# schaltplan.net
KiCad netlist of a schematic drawn in EAGLE
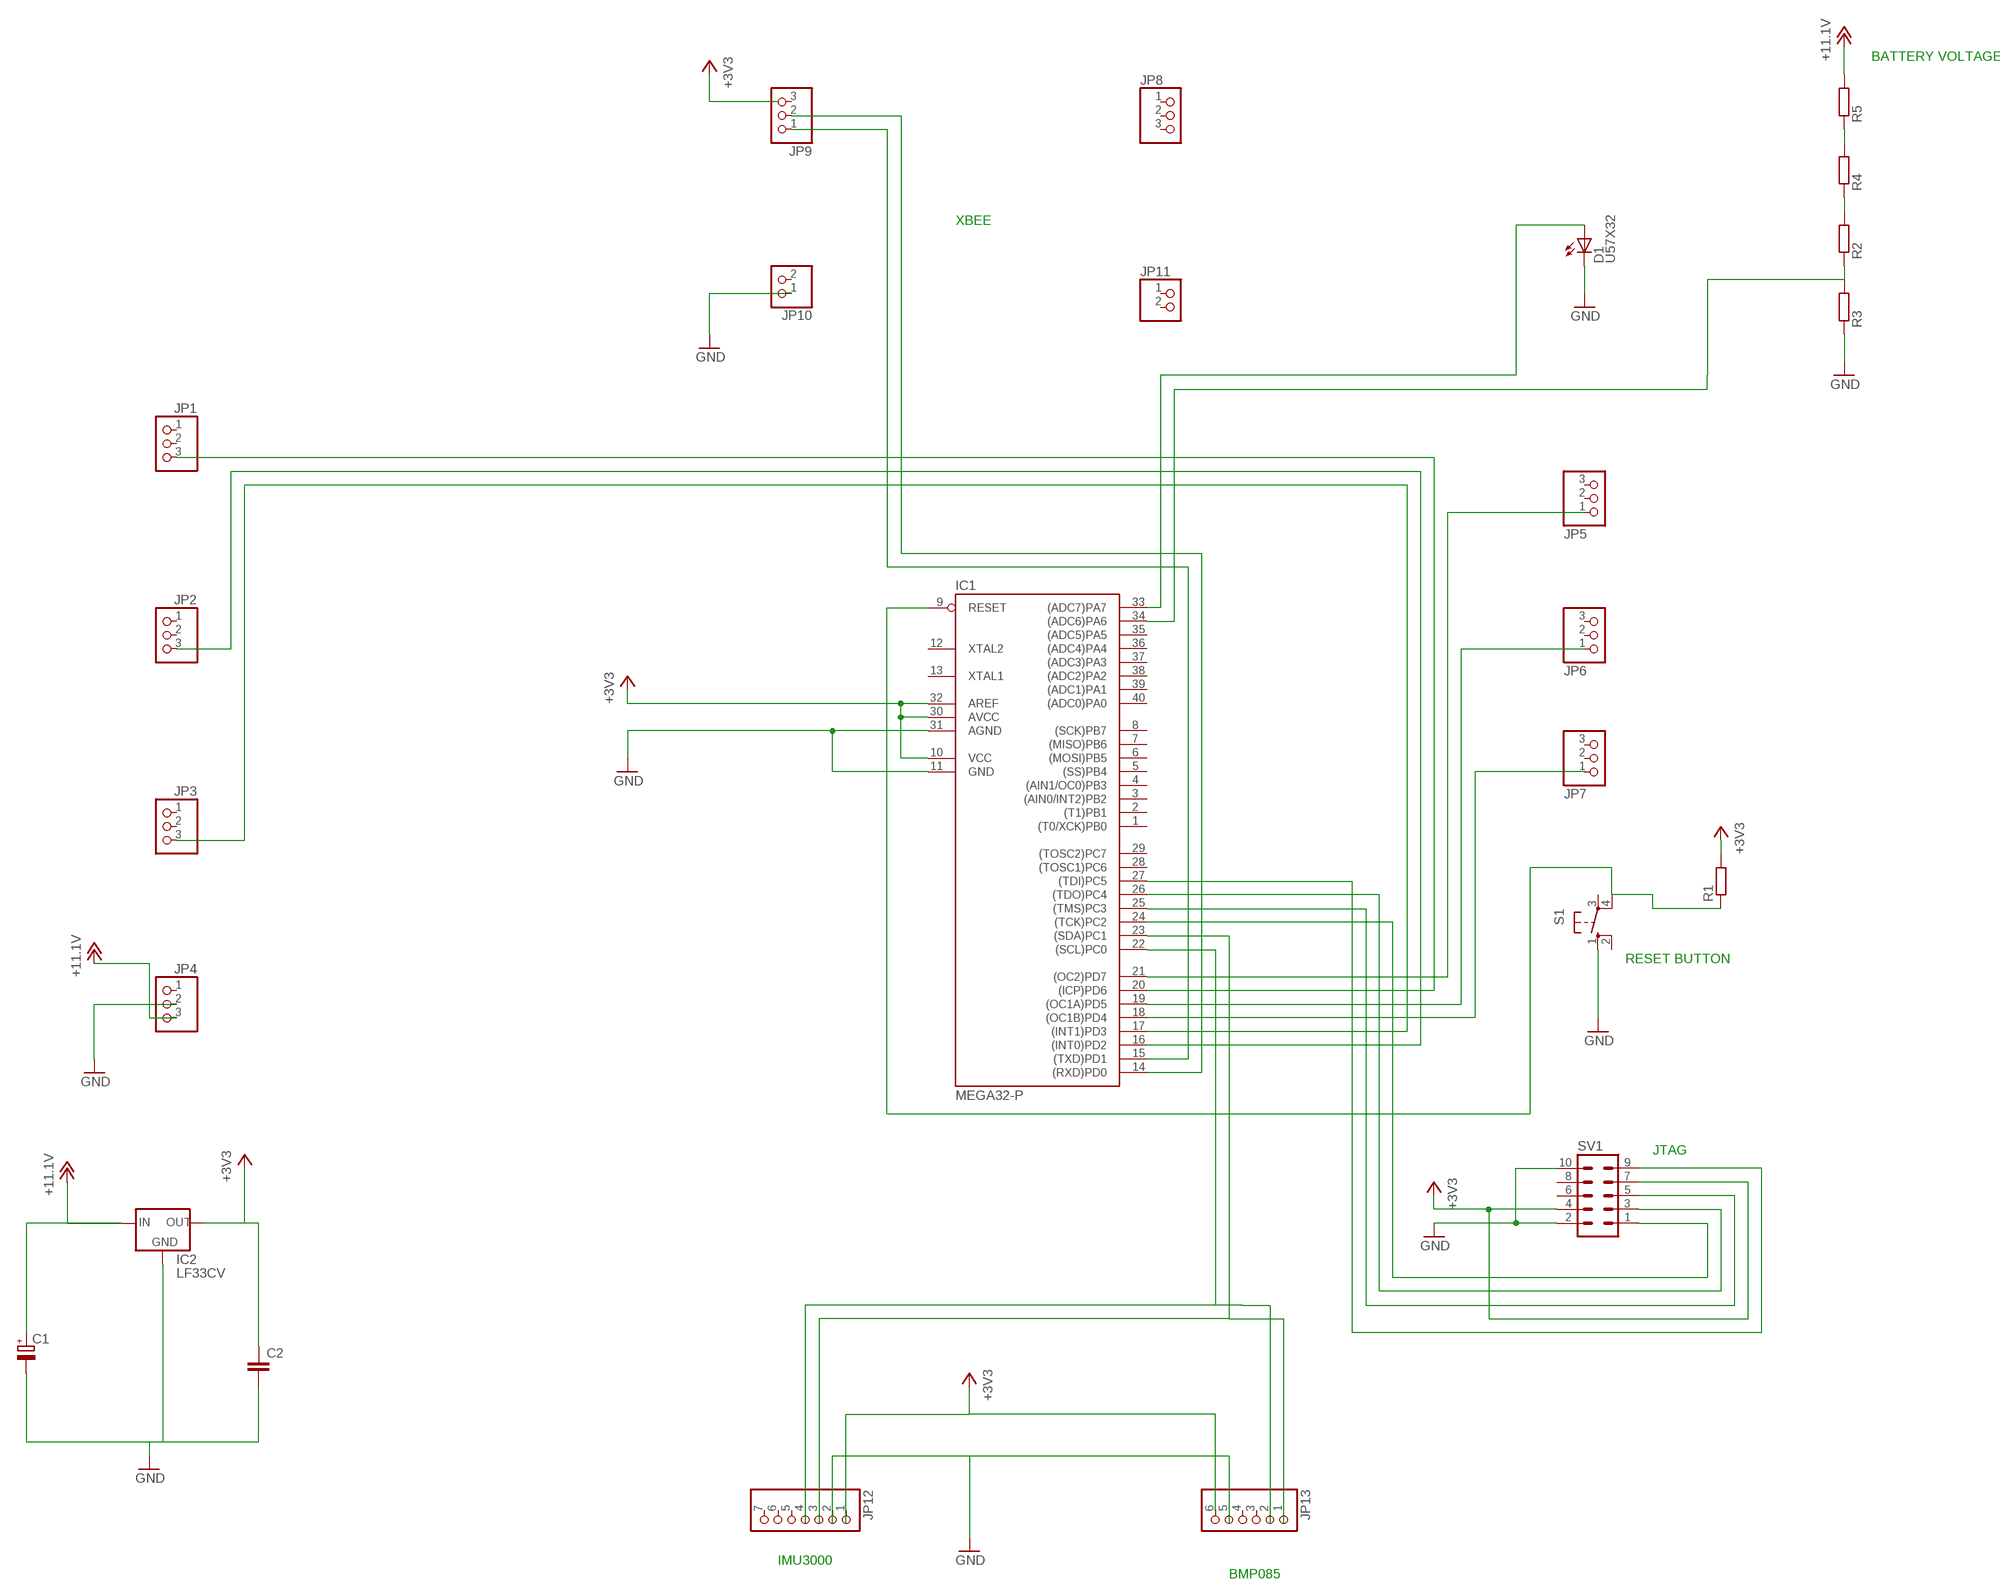
[diagram p0: schematic, sheet 1]

(export (version "E")
  (design (tool "Eeschema 10.0.6"))
  (components
    (comp (ref "C1")
      (value "CPOL-EU085CS-1AR")
      (footprint "eagle-import:085CS_1AR")
      (libsource (lib "eagle-import") (part "CPOL-EU085CS-1AR"))
    )
    (comp (ref "C2")
      (value "C-EU025-024X044")
      (footprint "eagle-import:C025-024X044")
      (libsource (lib "eagle-import") (part "C-EU025-024X044"))
    )
    (comp (ref "D1")
      (value "U57X32")
      (footprint "eagle-import:U57X32")
      (libsource (lib "eagle-import") (part "U57X32"))
    )
    (comp (ref "IC1")
      (value "MEGA32-P")
      (footprint "eagle-import:DIL40")
      (libsource (lib "eagle-import") (part "MEGA32-P"))
    )
    (comp (ref "IC2")
      (value "LF33CV")
      (footprint "eagle-import:78XXL")
      (libsource (lib "eagle-import") (part "78XXL"))
    )
    (comp (ref "JP1")
      (value "PINHD-1X3")
      (footprint "eagle-import:1X03")
      (libsource (lib "eagle-import") (part "PINHD-1X3"))
    )
    (comp (ref "JP2")
      (value "PINHD-1X3")
      (footprint "eagle-import:1X03")
      (libsource (lib "eagle-import") (part "PINHD-1X3"))
    )
    (comp (ref "JP3")
      (value "PINHD-1X3")
      (footprint "eagle-import:1X03")
      (libsource (lib "eagle-import") (part "PINHD-1X3"))
    )
    (comp (ref "JP4")
      (value "PINHD-1X3")
      (footprint "eagle-import:1X03")
      (libsource (lib "eagle-import") (part "PINHD-1X3"))
    )
    (comp (ref "JP5")
      (value "PINHD-1X3")
      (footprint "eagle-import:1X03")
      (libsource (lib "eagle-import") (part "PINHD-1X3"))
    )
    (comp (ref "JP6")
      (value "PINHD-1X3")
      (footprint "eagle-import:1X03")
      (libsource (lib "eagle-import") (part "PINHD-1X3"))
    )
    (comp (ref "JP7")
      (value "PINHD-1X3")
      (footprint "eagle-import:1X03")
      (libsource (lib "eagle-import") (part "PINHD-1X3"))
    )
    (comp (ref "JP8")
      (value "PINHD-1X3")
      (footprint "eagle-import:1X03")
      (libsource (lib "eagle-import") (part "PINHD-1X3"))
    )
    (comp (ref "JP9")
      (value "PINHD-1X3")
      (footprint "eagle-import:1X03")
      (libsource (lib "eagle-import") (part "PINHD-1X3"))
    )
    (comp (ref "JP10")
      (value "PINHD-1X2")
      (footprint "eagle-import:1X02")
      (libsource (lib "eagle-import") (part "PINHD-1X2"))
    )
    (comp (ref "JP11")
      (value "PINHD-1X2")
      (footprint "eagle-import:1X02")
      (libsource (lib "eagle-import") (part "PINHD-1X2"))
    )
    (comp (ref "JP12")
      (value "PINHD-1X7")
      (footprint "eagle-import:1X07")
      (libsource (lib "eagle-import") (part "PINHD-1X7"))
    )
    (comp (ref "JP13")
      (value "PINHD-1X6")
      (footprint "eagle-import:1X06")
      (libsource (lib "eagle-import") (part "PINHD-1X6"))
    )
    (comp (ref "R1")
      (value "R-EU_0204/2V")
      (footprint "eagle-import:0204V")
      (libsource (lib "eagle-import") (part "R-EU_0204/2V"))
    )
    (comp (ref "R2")
      (value "R-EU_0204/2V")
      (footprint "eagle-import:0204V")
      (libsource (lib "eagle-import") (part "R-EU_0204/2V"))
    )
    (comp (ref "R3")
      (value "R-EU_0204/2V")
      (footprint "eagle-import:0204V")
      (libsource (lib "eagle-import") (part "R-EU_0204/2V"))
    )
    (comp (ref "R4")
      (value "R-EU_0204/2V")
      (footprint "eagle-import:0204V")
      (libsource (lib "eagle-import") (part "R-EU_0204/2V"))
    )
    (comp (ref "R5")
      (value "R-EU_0204/2V")
      (footprint "eagle-import:0204V")
      (libsource (lib "eagle-import") (part "R-EU_0204/2V"))
    )
    (comp (ref "S1")
      (value "40-XX")
      (footprint "eagle-import:B3F-40XX")
      (fields (field (name "MF") "OMRON COMPONENTS USA") (field (name "MPN") "B3F-4000"))
      (libsource (lib "eagle-import") (part "40-XX"))
    )
    (comp (ref "SV1")
      (value "ML10")
      (footprint "eagle-import:ML10")
      (libsource (lib "eagle-import") (part "ML10"))
    )
  )
  (nets
    (net (code "1") (name "+3V3") (class "Default")
      (node (ref "C2") (pin "1") (pinfunction "1_1") (pintype "passive"))
      (node (ref "IC1") (pin "10") (pinfunction "VCC_10") (pintype "power_in"))
      (node (ref "IC1") (pin "30") (pinfunction "AVCC_30") (pintype "power_in"))
      (node (ref "IC1") (pin "32") (pinfunction "AREF_32") (pintype "power_in"))
      (node (ref "IC2") (pin "OUT") (pinfunction "OUT_OUT") (pintype "passive"))
      (node (ref "JP13") (pin "6") (pinfunction "6_6") (pintype "passive"))
      (node (ref "R1") (pin "2") (pinfunction "2_2") (pintype "passive"))
      (node (ref "SV1") (pin "4") (pinfunction "4_4") (pintype "passive"))
      (node (ref "SV1") (pin "7") (pinfunction "7_7") (pintype "passive"))
    )
    (net (code "2") (name "+11.1V") (class "Default")
      (node (ref "C1") (pin "+") (pinfunction "+_+") (pintype "passive"))
      (node (ref "IC2") (pin "IN") (pinfunction "IN_IN") (pintype "input"))
      (node (ref "JP4") (pin "3") (pinfunction "3_3") (pintype "passive"))
      (node (ref "R5") (pin "2") (pinfunction "2_2") (pintype "passive"))
    )
    (net (code "3") (name "GND") (class "Default")
      (node (ref "C1") (pin "-") (pinfunction "-_-") (pintype "passive"))
      (node (ref "C2") (pin "2") (pinfunction "2_2") (pintype "passive"))
      (node (ref "D1") (pin "K") (pinfunction "C_K") (pintype "passive"))
      (node (ref "IC1") (pin "11") (pinfunction "GND_11") (pintype "power_in"))
      (node (ref "IC1") (pin "31") (pinfunction "AGND_31") (pintype "power_in"))
      (node (ref "IC2") (pin "GND") (pinfunction "GND_GND") (pintype "input"))
      (node (ref "JP10") (pin "1") (pinfunction "1_1") (pintype "passive"))
      (node (ref "JP4") (pin "2") (pinfunction "2_2") (pintype "passive"))
      (node (ref "R3") (pin "1") (pinfunction "1_1") (pintype "passive"))
      (node (ref "S1") (pin "1") (pinfunction "S_1") (pintype "passive"))
      (node (ref "SV1") (pin "10") (pinfunction "10_10") (pintype "passive"))
      (node (ref "SV1") (pin "2") (pinfunction "2_2") (pintype "passive"))
    )
    (net (code "4") (name "Net-(IC1-(ADC6)PA6)") (class "Default")
      (node (ref "IC1") (pin "34") (pinfunction "(ADC6)PA6_34") (pintype "bidirectional"))
      (node (ref "R2") (pin "1") (pinfunction "1_1") (pintype "passive"))
      (node (ref "R3") (pin "2") (pinfunction "2_2") (pintype "passive"))
    )
    (net (code "5") (name "Net-(IC1-(ADC7)PA7)") (class "Default")
      (node (ref "D1") (pin "A") (pinfunction "A_A") (pintype "passive"))
      (node (ref "IC1") (pin "33") (pinfunction "(ADC7)PA7_33") (pintype "bidirectional"))
    )
    (net (code "6") (name "Net-(IC1-(ICP)PD6)") (class "Default")
      (node (ref "IC1") (pin "20") (pinfunction "(ICP)PD6_20") (pintype "bidirectional"))
      (node (ref "JP1") (pin "3") (pinfunction "3_3") (pintype "passive"))
    )
    (net (code "7") (name "Net-(IC1-(INT0)PD2)") (class "Default")
      (node (ref "IC1") (pin "16") (pinfunction "(INT0)PD2_16") (pintype "bidirectional"))
      (node (ref "JP2") (pin "3") (pinfunction "3_3") (pintype "passive"))
    )
    (net (code "8") (name "Net-(IC1-(INT1)PD3)") (class "Default")
      (node (ref "IC1") (pin "17") (pinfunction "(INT1)PD3_17") (pintype "bidirectional"))
      (node (ref "JP3") (pin "3") (pinfunction "3_3") (pintype "passive"))
    )
    (net (code "9") (name "Net-(IC1-(OC1A)PD5)") (class "Default")
      (node (ref "IC1") (pin "19") (pinfunction "(OC1A)PD5_19") (pintype "bidirectional"))
      (node (ref "JP6") (pin "1") (pinfunction "1_1") (pintype "passive"))
    )
    (net (code "10") (name "Net-(IC1-(OC1B)PD4)") (class "Default")
      (node (ref "IC1") (pin "18") (pinfunction "(OC1B)PD4_18") (pintype "bidirectional"))
      (node (ref "JP7") (pin "1") (pinfunction "1_1") (pintype "passive"))
    )
    (net (code "11") (name "Net-(IC1-(OC2)PD7)") (class "Default")
      (node (ref "IC1") (pin "21") (pinfunction "(OC2)PD7_21") (pintype "bidirectional"))
      (node (ref "JP5") (pin "1") (pinfunction "1_1") (pintype "passive"))
    )
    (net (code "12") (name "Net-(IC1-(RXD)PD0)") (class "Default")
      (node (ref "IC1") (pin "14") (pinfunction "(RXD)PD0_14") (pintype "bidirectional"))
      (node (ref "JP9") (pin "2") (pinfunction "2_2") (pintype "passive"))
    )
    (net (code "13") (name "Net-(IC1-(TCK)PC2)") (class "Default")
      (node (ref "IC1") (pin "24") (pinfunction "(TCK)PC2_24") (pintype "bidirectional"))
      (node (ref "SV1") (pin "1") (pinfunction "1_1") (pintype "passive"))
    )
    (net (code "14") (name "Net-(IC1-(TDI)PC5)") (class "Default")
      (node (ref "IC1") (pin "27") (pinfunction "(TDI)PC5_27") (pintype "bidirectional"))
      (node (ref "SV1") (pin "9") (pinfunction "9_9") (pintype "passive"))
    )
    (net (code "15") (name "Net-(IC1-(TDO)PC4)") (class "Default")
      (node (ref "IC1") (pin "26") (pinfunction "(TDO)PC4_26") (pintype "bidirectional"))
      (node (ref "SV1") (pin "3") (pinfunction "3_3") (pintype "passive"))
    )
    (net (code "16") (name "Net-(IC1-(TMS)PC3)") (class "Default")
      (node (ref "IC1") (pin "25") (pinfunction "(TMS)PC3_25") (pintype "bidirectional"))
      (node (ref "SV1") (pin "5") (pinfunction "5_5") (pintype "passive"))
    )
    (net (code "17") (name "Net-(IC1-(TXD)PD1)") (class "Default")
      (node (ref "IC1") (pin "15") (pinfunction "(TXD)PD1_15") (pintype "bidirectional"))
      (node (ref "JP9") (pin "1") (pinfunction "1_1") (pintype "passive"))
    )
    (net (code "18") (name "Net-(IC1-RESET)") (class "Default")
      (node (ref "IC1") (pin "9") (pinfunction "RESET_9") (pintype "input"))
      (node (ref "R1") (pin "1") (pinfunction "1_1") (pintype "passive"))
      (node (ref "S1") (pin "4") (pinfunction "P1_4") (pintype "passive"))
    )
    (net (code "19") (name "Net-(R2-Pad2)") (class "Default")
      (node (ref "R2") (pin "2") (pinfunction "2_2") (pintype "passive"))
      (node (ref "R4") (pin "1") (pinfunction "1_1") (pintype "passive"))
    )
    (net (code "20") (name "Net-(R4-Pad2)") (class "Default")
      (node (ref "R4") (pin "2") (pinfunction "2_2") (pintype "passive"))
      (node (ref "R5") (pin "1") (pinfunction "1_1") (pintype "passive"))
    )
    (net (code "21") (name "unconnected-(IC1-(ADC0)PA0-Pad40)") (class "Default")
      (node (ref "IC1") (pin "40") (pinfunction "(ADC0)PA0_40") (pintype "bidirectional"))
    )
    (net (code "22") (name "unconnected-(IC1-(ADC1)PA1-Pad39)") (class "Default")
      (node (ref "IC1") (pin "39") (pinfunction "(ADC1)PA1_39") (pintype "bidirectional"))
    )
    (net (code "23") (name "unconnected-(IC1-(ADC2)PA2-Pad38)") (class "Default")
      (node (ref "IC1") (pin "38") (pinfunction "(ADC2)PA2_38") (pintype "bidirectional"))
    )
    (net (code "24") (name "unconnected-(IC1-(ADC3)PA3-Pad37)") (class "Default")
      (node (ref "IC1") (pin "37") (pinfunction "(ADC3)PA3_37") (pintype "bidirectional"))
    )
    (net (code "25") (name "unconnected-(IC1-(ADC4)PA4-Pad36)") (class "Default")
      (node (ref "IC1") (pin "36") (pinfunction "(ADC4)PA4_36") (pintype "bidirectional"))
    )
    (net (code "26") (name "unconnected-(IC1-(ADC5)PA5-Pad35)") (class "Default")
      (node (ref "IC1") (pin "35") (pinfunction "(ADC5)PA5_35") (pintype "bidirectional"))
    )
    (net (code "27") (name "unconnected-(IC1-(AIN0{slash}INT2)PB2-Pad3)") (class "Default")
      (node (ref "IC1") (pin "3") (pinfunction "(AIN0/INT2)PB2_3") (pintype "bidirectional"))
    )
    (net (code "28") (name "unconnected-(IC1-(AIN1{slash}OC0)PB3-Pad4)") (class "Default")
      (node (ref "IC1") (pin "4") (pinfunction "(AIN1/OC0)PB3_4") (pintype "bidirectional"))
    )
    (net (code "29") (name "unconnected-(IC1-(MISO)PB6-Pad7)") (class "Default")
      (node (ref "IC1") (pin "7") (pinfunction "(MISO)PB6_7") (pintype "bidirectional"))
    )
    (net (code "30") (name "unconnected-(IC1-(MOSI)PB5-Pad6)") (class "Default")
      (node (ref "IC1") (pin "6") (pinfunction "(MOSI)PB5_6") (pintype "bidirectional"))
    )
    (net (code "31") (name "unconnected-(IC1-(SCK)PB7-Pad8)") (class "Default")
      (node (ref "IC1") (pin "8") (pinfunction "(SCK)PB7_8") (pintype "bidirectional"))
    )
    (net (code "32") (name "unconnected-(IC1-(SCL)PC0-Pad22)") (class "Default")
      (node (ref "IC1") (pin "22") (pinfunction "(SCL)PC0_22") (pintype "bidirectional"))
    )
    (net (code "33") (name "unconnected-(IC1-(SDA)PC1-Pad23)") (class "Default")
      (node (ref "IC1") (pin "23") (pinfunction "(SDA)PC1_23") (pintype "bidirectional"))
    )
    (net (code "34") (name "unconnected-(IC1-(SS)PB4-Pad5)") (class "Default")
      (node (ref "IC1") (pin "5") (pinfunction "(SS)PB4_5") (pintype "bidirectional"))
    )
    (net (code "35") (name "unconnected-(IC1-(T0{slash}XCK)PB0-Pad1)") (class "Default")
      (node (ref "IC1") (pin "1") (pinfunction "(T0/XCK)PB0_1") (pintype "bidirectional"))
    )
    (net (code "36") (name "unconnected-(IC1-(T1)PB1-Pad2)") (class "Default")
      (node (ref "IC1") (pin "2") (pinfunction "(T1)PB1_2") (pintype "bidirectional"))
    )
    (net (code "37") (name "unconnected-(IC1-(TOSC1)PC6-Pad28)") (class "Default")
      (node (ref "IC1") (pin "28") (pinfunction "(TOSC1)PC6_28") (pintype "bidirectional"))
    )
    (net (code "38") (name "unconnected-(IC1-(TOSC2)PC7-Pad29)") (class "Default")
      (node (ref "IC1") (pin "29") (pinfunction "(TOSC2)PC7_29") (pintype "bidirectional"))
    )
    (net (code "39") (name "unconnected-(IC1-XTAL1-Pad13)") (class "Default")
      (node (ref "IC1") (pin "13") (pinfunction "XTAL1_13") (pintype "bidirectional"))
    )
    (net (code "40") (name "unconnected-(IC1-XTAL2-Pad12)") (class "Default")
      (node (ref "IC1") (pin "12") (pinfunction "XTAL2_12") (pintype "bidirectional"))
    )
    (net (code "41") (name "unconnected-(JP1-Pad1)") (class "Default")
      (node (ref "JP1") (pin "1") (pinfunction "1_1") (pintype "passive"))
    )
    (net (code "42") (name "unconnected-(JP1-Pad2)") (class "Default")
      (node (ref "JP1") (pin "2") (pinfunction "2_2") (pintype "passive"))
    )
    (net (code "43") (name "unconnected-(JP2-Pad1)") (class "Default")
      (node (ref "JP2") (pin "1") (pinfunction "1_1") (pintype "passive"))
    )
    (net (code "44") (name "unconnected-(JP2-Pad2)") (class "Default")
      (node (ref "JP2") (pin "2") (pinfunction "2_2") (pintype "passive"))
    )
    (net (code "45") (name "unconnected-(JP3-Pad1)") (class "Default")
      (node (ref "JP3") (pin "1") (pinfunction "1_1") (pintype "passive"))
    )
    (net (code "46") (name "unconnected-(JP3-Pad2)") (class "Default")
      (node (ref "JP3") (pin "2") (pinfunction "2_2") (pintype "passive"))
    )
    (net (code "47") (name "unconnected-(JP4-Pad1)") (class "Default")
      (node (ref "JP4") (pin "1") (pinfunction "1_1") (pintype "passive"))
    )
    (net (code "48") (name "unconnected-(JP5-Pad2)") (class "Default")
      (node (ref "JP5") (pin "2") (pinfunction "2_2") (pintype "passive"))
    )
    (net (code "49") (name "unconnected-(JP5-Pad3)") (class "Default")
      (node (ref "JP5") (pin "3") (pinfunction "3_3") (pintype "passive"))
    )
    (net (code "50") (name "unconnected-(JP6-Pad2)") (class "Default")
      (node (ref "JP6") (pin "2") (pinfunction "2_2") (pintype "passive"))
    )
    (net (code "51") (name "unconnected-(JP6-Pad3)") (class "Default")
      (node (ref "JP6") (pin "3") (pinfunction "3_3") (pintype "passive"))
    )
    (net (code "52") (name "unconnected-(JP7-Pad2)") (class "Default")
      (node (ref "JP7") (pin "2") (pinfunction "2_2") (pintype "passive"))
    )
    (net (code "53") (name "unconnected-(JP7-Pad3)") (class "Default")
      (node (ref "JP7") (pin "3") (pinfunction "3_3") (pintype "passive"))
    )
    (net (code "54") (name "unconnected-(JP8-Pad1)") (class "Default")
      (node (ref "JP8") (pin "1") (pinfunction "1_1") (pintype "passive"))
    )
    (net (code "55") (name "unconnected-(JP8-Pad2)") (class "Default")
      (node (ref "JP8") (pin "2") (pinfunction "2_2") (pintype "passive"))
    )
    (net (code "56") (name "unconnected-(JP8-Pad3)") (class "Default")
      (node (ref "JP8") (pin "3") (pinfunction "3_3") (pintype "passive"))
    )
    (net (code "57") (name "unconnected-(JP9-Pad3)") (class "Default")
      (node (ref "JP9") (pin "3") (pinfunction "3_3") (pintype "passive"))
    )
    (net (code "58") (name "unconnected-(JP10-Pad2)") (class "Default")
      (node (ref "JP10") (pin "2") (pinfunction "2_2") (pintype "passive"))
    )
    (net (code "59") (name "unconnected-(JP11-Pad1)") (class "Default")
      (node (ref "JP11") (pin "1") (pinfunction "1_1") (pintype "passive"))
    )
    (net (code "60") (name "unconnected-(JP11-Pad2)") (class "Default")
      (node (ref "JP11") (pin "2") (pinfunction "2_2") (pintype "passive"))
    )
    (net (code "61") (name "unconnected-(JP12-Pad1)") (class "Default")
      (node (ref "JP12") (pin "1") (pinfunction "1_1") (pintype "passive"))
    )
    (net (code "62") (name "unconnected-(JP12-Pad2)") (class "Default")
      (node (ref "JP12") (pin "2") (pinfunction "2_2") (pintype "passive"))
    )
    (net (code "63") (name "unconnected-(JP12-Pad3)") (class "Default")
      (node (ref "JP12") (pin "3") (pinfunction "3_3") (pintype "passive"))
    )
    (net (code "64") (name "unconnected-(JP12-Pad4)") (class "Default")
      (node (ref "JP12") (pin "4") (pinfunction "4_4") (pintype "passive"))
    )
    (net (code "65") (name "unconnected-(JP12-Pad5)") (class "Default")
      (node (ref "JP12") (pin "5") (pinfunction "5_5") (pintype "passive"))
    )
    (net (code "66") (name "unconnected-(JP12-Pad6)") (class "Default")
      (node (ref "JP12") (pin "6") (pinfunction "6_6") (pintype "passive"))
    )
    (net (code "67") (name "unconnected-(JP12-Pad7)") (class "Default")
      (node (ref "JP12") (pin "7") (pinfunction "7_7") (pintype "passive"))
    )
    (net (code "68") (name "unconnected-(JP13-Pad1)") (class "Default")
      (node (ref "JP13") (pin "1") (pinfunction "1_1") (pintype "passive"))
    )
    (net (code "69") (name "unconnected-(JP13-Pad2)") (class "Default")
      (node (ref "JP13") (pin "2") (pinfunction "2_2") (pintype "passive"))
    )
    (net (code "70") (name "unconnected-(JP13-Pad3)") (class "Default")
      (node (ref "JP13") (pin "3") (pinfunction "3_3") (pintype "passive"))
    )
    (net (code "71") (name "unconnected-(JP13-Pad4)") (class "Default")
      (node (ref "JP13") (pin "4") (pinfunction "4_4") (pintype "passive"))
    )
    (net (code "72") (name "unconnected-(JP13-Pad5)") (class "Default")
      (node (ref "JP13") (pin "5") (pinfunction "5_5") (pintype "passive"))
    )
    (net (code "73") (name "unconnected-(S1-P-Pad3)") (class "Default")
      (node (ref "S1") (pin "3") (pinfunction "P_3") (pintype "passive"))
    )
    (net (code "74") (name "unconnected-(S1-S1-Pad2)") (class "Default")
      (node (ref "S1") (pin "2") (pinfunction "S1_2") (pintype "passive"))
    )
    (net (code "75") (name "unconnected-(SV1-Pad6)") (class "Default")
      (node (ref "SV1") (pin "6") (pinfunction "6_6") (pintype "passive"))
    )
    (net (code "76") (name "unconnected-(SV1-Pad8)") (class "Default")
      (node (ref "SV1") (pin "8") (pinfunction "8_8") (pintype "passive"))
    )
  )
)
